# GimbalControl.net
KiCad netlist of a schematic drawn in EAGLE
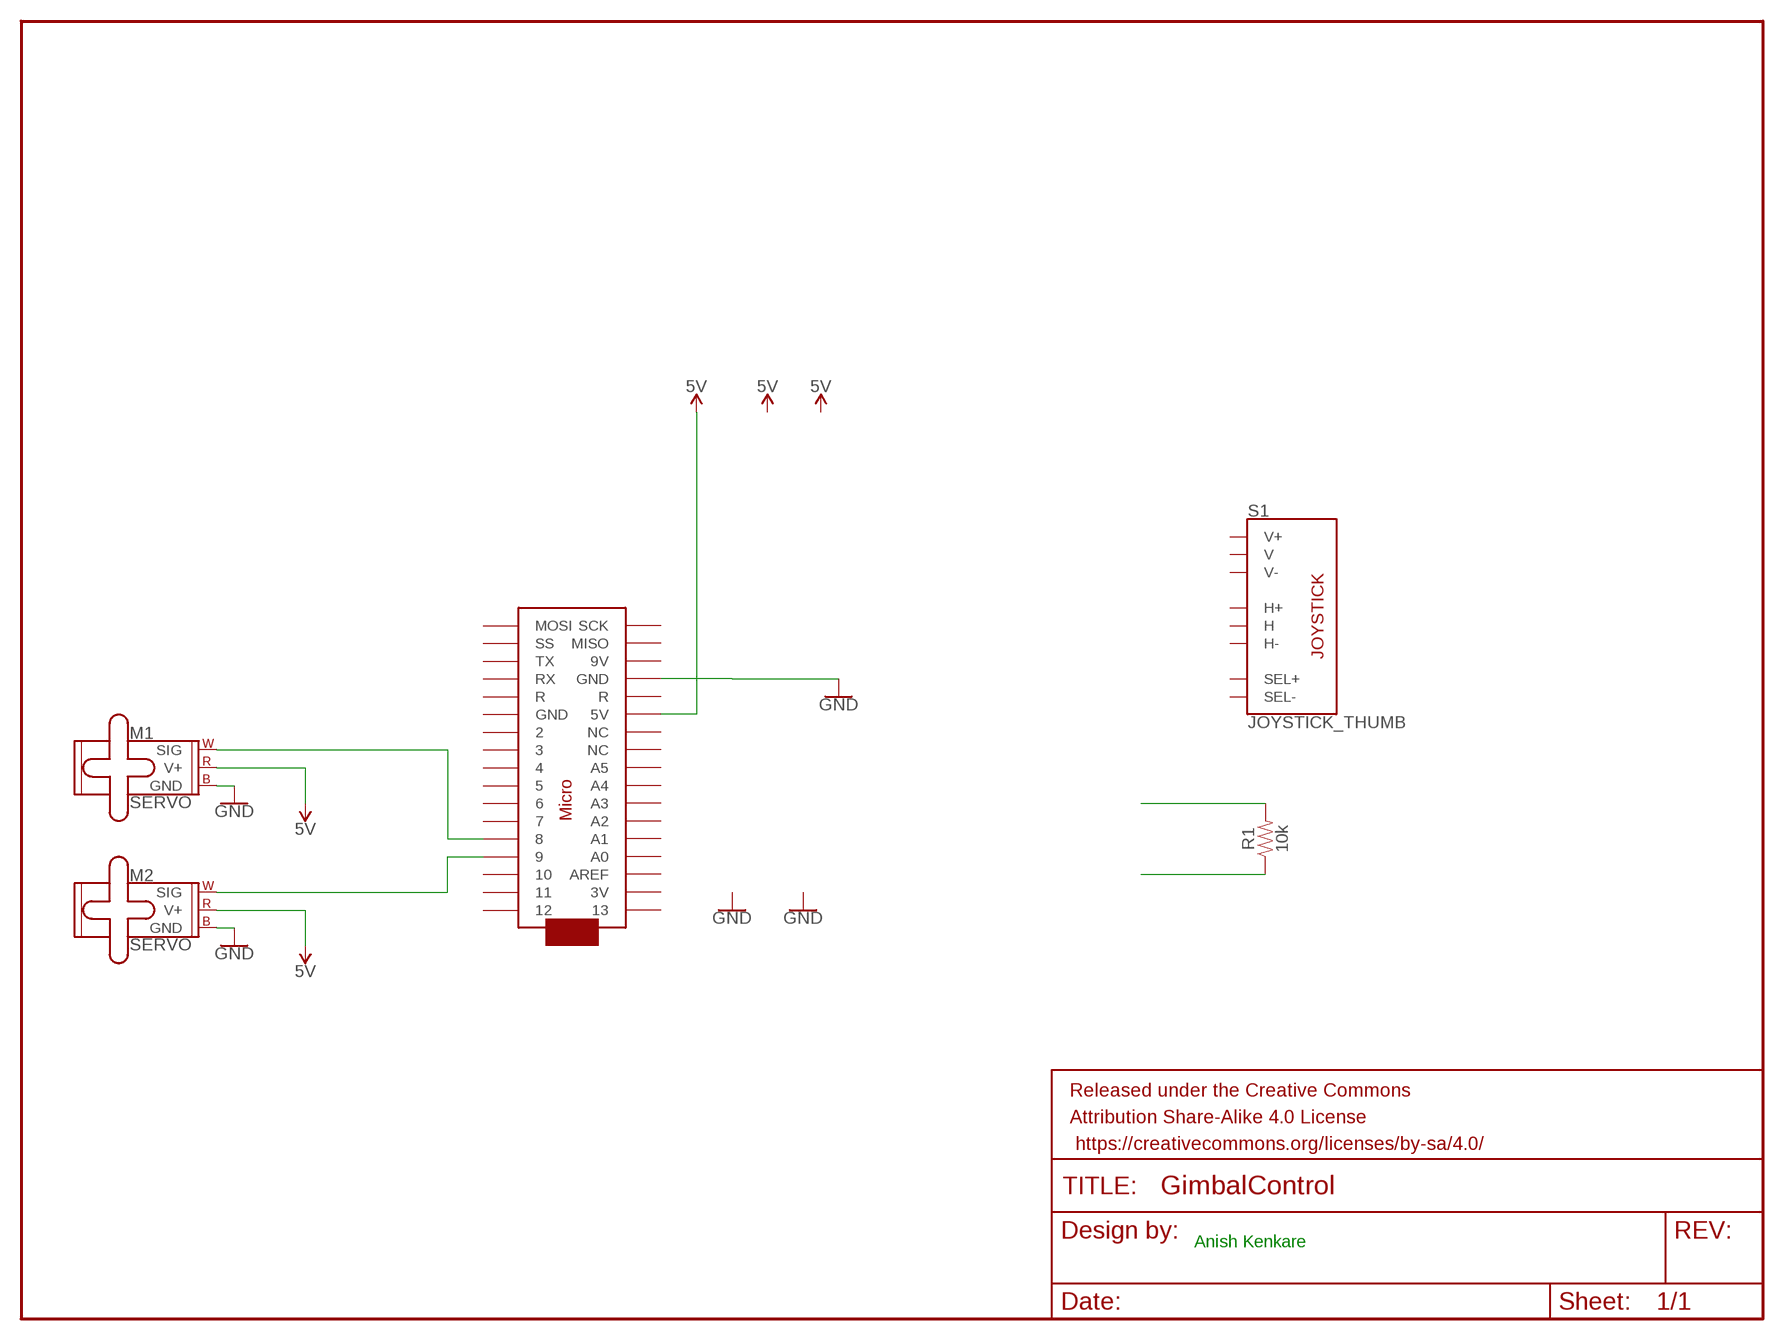
[diagram p0: schematic, sheet 1]

(export (version "E")
  (design (tool "Eeschema 10.0.6"))
  (components
    (comp (ref "FRAME1")
      (value "FRAME-LETTER")
      (footprint "eagle-import:CREATIVE_COMMONS")
      (libsource (lib "eagle-import") (part "FRAME-LETTER"))
    )
    (comp (ref "M1")
      (value "SERVO")
      (footprint "eagle-import:1X03")
      (libsource (lib "eagle-import") (part "SERVO"))
    )
    (comp (ref "M2")
      (value "SERVO")
      (footprint "eagle-import:1X03")
      (libsource (lib "eagle-import") (part "SERVO"))
    )
    (comp (ref "R1")
      (value "10k")
      (footprint "eagle-import:AXIAL-0.3")
      (libsource (lib "eagle-import") (part "10KOHM-HORIZ-1/4W-1%"))
    )
    (comp (ref "S1")
      (value "JOYSTICK_THUMB")
      (footprint "eagle-import:JOYSTICK")
      (libsource (lib "eagle-import") (part "JOYSTICK_THUMB"))
    )
    (comp (ref "U$1")
      (value "ARDUINOMICRO")
      (footprint "eagle-import:ARDUINOMICRO")
      (libsource (lib "eagle-import") (part "ARDUINOMICRO"))
    )
  )
  (nets
    (net (code "1") (name "5V") (class "Default")
      (node (ref "M1") (pin "2") (pinfunction "V+_2") (pintype "bidirectional"))
      (node (ref "M2") (pin "2") (pinfunction "V+_2") (pintype "bidirectional"))
      (node (ref "U$1") (pin "P$23") (pinfunction "5V_P$23") (pintype "bidirectional"))
    )
    (net (code "2") (name "GND") (class "Default")
      (node (ref "M1") (pin "3") (pinfunction "GND_3") (pintype "bidirectional"))
      (node (ref "M2") (pin "3") (pinfunction "GND_3") (pintype "bidirectional"))
      (node (ref "U$1") (pin "P$12") (pinfunction "GND_P$12") (pintype "bidirectional"))
    )
    (net (code "3") (name "Net-(M1-SIG)") (class "Default")
      (node (ref "M1") (pin "1") (pinfunction "SIG_1") (pintype "bidirectional"))
      (node (ref "U$1") (pin "P$5") (pinfunction "8_P$5") (pintype "bidirectional"))
    )
    (net (code "4") (name "Net-(M2-SIG)") (class "Default")
      (node (ref "M2") (pin "1") (pinfunction "SIG_1") (pintype "bidirectional"))
      (node (ref "U$1") (pin "P$4") (pinfunction "9_P$4") (pintype "bidirectional"))
    )
    (net (code "5") (name "unconnected-(R1-1-PadP$1)") (class "Default")
      (node (ref "R1") (pin "P$1") (pinfunction "1_P$1") (pintype "passive"))
    )
    (net (code "6") (name "unconnected-(R1-2-PadP$2)") (class "Default")
      (node (ref "R1") (pin "P$2") (pinfunction "2_P$2") (pintype "passive"))
    )
    (net (code "7") (name "unconnected-(S1-H+-PadH1)") (class "Default")
      (node (ref "S1") (pin "H1") (pinfunction "H+_H1") (pintype "bidirectional"))
    )
    (net (code "8") (name "unconnected-(S1-H--PadH3)") (class "Default")
      (node (ref "S1") (pin "H3") (pinfunction "H-_H3") (pintype "bidirectional"))
    )
    (net (code "9") (name "unconnected-(S1-H-PadH2)") (class "Default")
      (node (ref "S1") (pin "H2") (pinfunction "H_H2") (pintype "bidirectional"))
    )
    (net (code "10") (name "unconnected-(S1-SEL+-PadB1A)") (class "Default")
      (node (ref "S1") (pin "B1A") (pinfunction "SEL+_B1A") (pintype "bidirectional"))
    )
    (net (code "11") (name "unconnected-(S1-SEL--PadB2A)") (class "Default")
      (node (ref "S1") (pin "B2A") (pinfunction "SEL-_B2A") (pintype "bidirectional"))
    )
    (net (code "12") (name "unconnected-(S1-V+-PadV1)") (class "Default")
      (node (ref "S1") (pin "V1") (pinfunction "V+_V1") (pintype "bidirectional"))
    )
    (net (code "13") (name "unconnected-(S1-V--PadV3)") (class "Default")
      (node (ref "S1") (pin "V3") (pinfunction "V-_V3") (pintype "bidirectional"))
    )
    (net (code "14") (name "unconnected-(S1-V-PadV2)") (class "Default")
      (node (ref "S1") (pin "V2") (pinfunction "V_V2") (pintype "bidirectional"))
    )
    (net (code "15") (name "unconnected-(U$1-2-PadP$11)") (class "Default")
      (node (ref "U$1") (pin "P$11") (pinfunction "2_P$11") (pintype "bidirectional"))
    )
    (net (code "16") (name "unconnected-(U$1-3-PadP$10)") (class "Default")
      (node (ref "U$1") (pin "P$10") (pinfunction "3_P$10") (pintype "bidirectional"))
    )
    (net (code "17") (name "unconnected-(U$1-3V-PadP$33)") (class "Default")
      (node (ref "U$1") (pin "P$33") (pinfunction "3V_P$33") (pintype "bidirectional"))
    )
    (net (code "18") (name "unconnected-(U$1-4-PadP$9)") (class "Default")
      (node (ref "U$1") (pin "P$9") (pinfunction "4_P$9") (pintype "bidirectional"))
    )
    (net (code "19") (name "unconnected-(U$1-5-PadP$8)") (class "Default")
      (node (ref "U$1") (pin "P$8") (pinfunction "5_P$8") (pintype "bidirectional"))
    )
    (net (code "20") (name "unconnected-(U$1-6-PadP$7)") (class "Default")
      (node (ref "U$1") (pin "P$7") (pinfunction "6_P$7") (pintype "bidirectional"))
    )
    (net (code "21") (name "unconnected-(U$1-7-PadP$6)") (class "Default")
      (node (ref "U$1") (pin "P$6") (pinfunction "7_P$6") (pintype "bidirectional"))
    )
    (net (code "22") (name "unconnected-(U$1-9V-PadP$20)") (class "Default")
      (node (ref "U$1") (pin "P$20") (pinfunction "9V_P$20") (pintype "bidirectional"))
    )
    (net (code "23") (name "unconnected-(U$1-10-PadP$3)") (class "Default")
      (node (ref "U$1") (pin "P$3") (pinfunction "10_P$3") (pintype "bidirectional"))
    )
    (net (code "24") (name "unconnected-(U$1-11-PadP$2)") (class "Default")
      (node (ref "U$1") (pin "P$2") (pinfunction "11_P$2") (pintype "bidirectional"))
    )
    (net (code "25") (name "unconnected-(U$1-12-PadP$1)") (class "Default")
      (node (ref "U$1") (pin "P$1") (pinfunction "12_P$1") (pintype "bidirectional"))
    )
    (net (code "26") (name "unconnected-(U$1-13-PadP$34)") (class "Default")
      (node (ref "U$1") (pin "P$34") (pinfunction "13_P$34") (pintype "bidirectional"))
    )
    (net (code "27") (name "unconnected-(U$1-A0-PadP$31)") (class "Default")
      (node (ref "U$1") (pin "P$31") (pinfunction "A0_P$31") (pintype "bidirectional"))
    )
    (net (code "28") (name "unconnected-(U$1-A1-PadP$30)") (class "Default")
      (node (ref "U$1") (pin "P$30") (pinfunction "A1_P$30") (pintype "bidirectional"))
    )
    (net (code "29") (name "unconnected-(U$1-A2-PadP$29)") (class "Default")
      (node (ref "U$1") (pin "P$29") (pinfunction "A2_P$29") (pintype "bidirectional"))
    )
    (net (code "30") (name "unconnected-(U$1-A3-PadP$28)") (class "Default")
      (node (ref "U$1") (pin "P$28") (pinfunction "A3_P$28") (pintype "bidirectional"))
    )
    (net (code "31") (name "unconnected-(U$1-A4-PadP$27)") (class "Default")
      (node (ref "U$1") (pin "P$27") (pinfunction "A4_P$27") (pintype "bidirectional"))
    )
    (net (code "32") (name "unconnected-(U$1-A5-PadP$26)") (class "Default")
      (node (ref "U$1") (pin "P$26") (pinfunction "A5_P$26") (pintype "bidirectional"))
    )
    (net (code "33") (name "unconnected-(U$1-AREF-PadP$32)") (class "Default")
      (node (ref "U$1") (pin "P$32") (pinfunction "AREF_P$32") (pintype "bidirectional"))
    )
    (net (code "34") (name "unconnected-(U$1-GND-PadP$21)") (class "Default")
      (node (ref "U$1") (pin "P$21") (pinfunction "GND_P$21") (pintype "bidirectional"))
    )
    (net (code "35") (name "unconnected-(U$1-MISO-PadP$19)") (class "Default")
      (node (ref "U$1") (pin "P$19") (pinfunction "MISO_P$19") (pintype "bidirectional"))
    )
    (net (code "36") (name "unconnected-(U$1-MOSI-PadP$17)") (class "Default")
      (node (ref "U$1") (pin "P$17") (pinfunction "MOSI_P$17") (pintype "bidirectional"))
    )
    (net (code "37") (name "unconnected-(U$1-NC-PadP$24)") (class "Default")
      (node (ref "U$1") (pin "P$24") (pinfunction "NC_P$24") (pintype "bidirectional"))
    )
    (net (code "38") (name "unconnected-(U$1-NC-PadP$25)") (class "Default")
      (node (ref "U$1") (pin "P$25") (pinfunction "NC_P$25") (pintype "bidirectional"))
    )
    (net (code "39") (name "unconnected-(U$1-R-PadP$13)") (class "Default")
      (node (ref "U$1") (pin "P$13") (pinfunction "R_P$13") (pintype "bidirectional"))
    )
    (net (code "40") (name "unconnected-(U$1-R-PadP$22)") (class "Default")
      (node (ref "U$1") (pin "P$22") (pinfunction "R_P$22") (pintype "bidirectional"))
    )
    (net (code "41") (name "unconnected-(U$1-RX-PadP$14)") (class "Default")
      (node (ref "U$1") (pin "P$14") (pinfunction "RX_P$14") (pintype "bidirectional"))
    )
    (net (code "42") (name "unconnected-(U$1-SCK-PadP$18)") (class "Default")
      (node (ref "U$1") (pin "P$18") (pinfunction "SCK_P$18") (pintype "bidirectional"))
    )
    (net (code "43") (name "unconnected-(U$1-SS-PadP$16)") (class "Default")
      (node (ref "U$1") (pin "P$16") (pinfunction "SS_P$16") (pintype "bidirectional"))
    )
    (net (code "44") (name "unconnected-(U$1-TX-PadP$15)") (class "Default")
      (node (ref "U$1") (pin "P$15") (pinfunction "TX_P$15") (pintype "bidirectional"))
    )
  )
)
